# Top_Level.net
KiCad netlist of a schematic drawn in Altium Designer
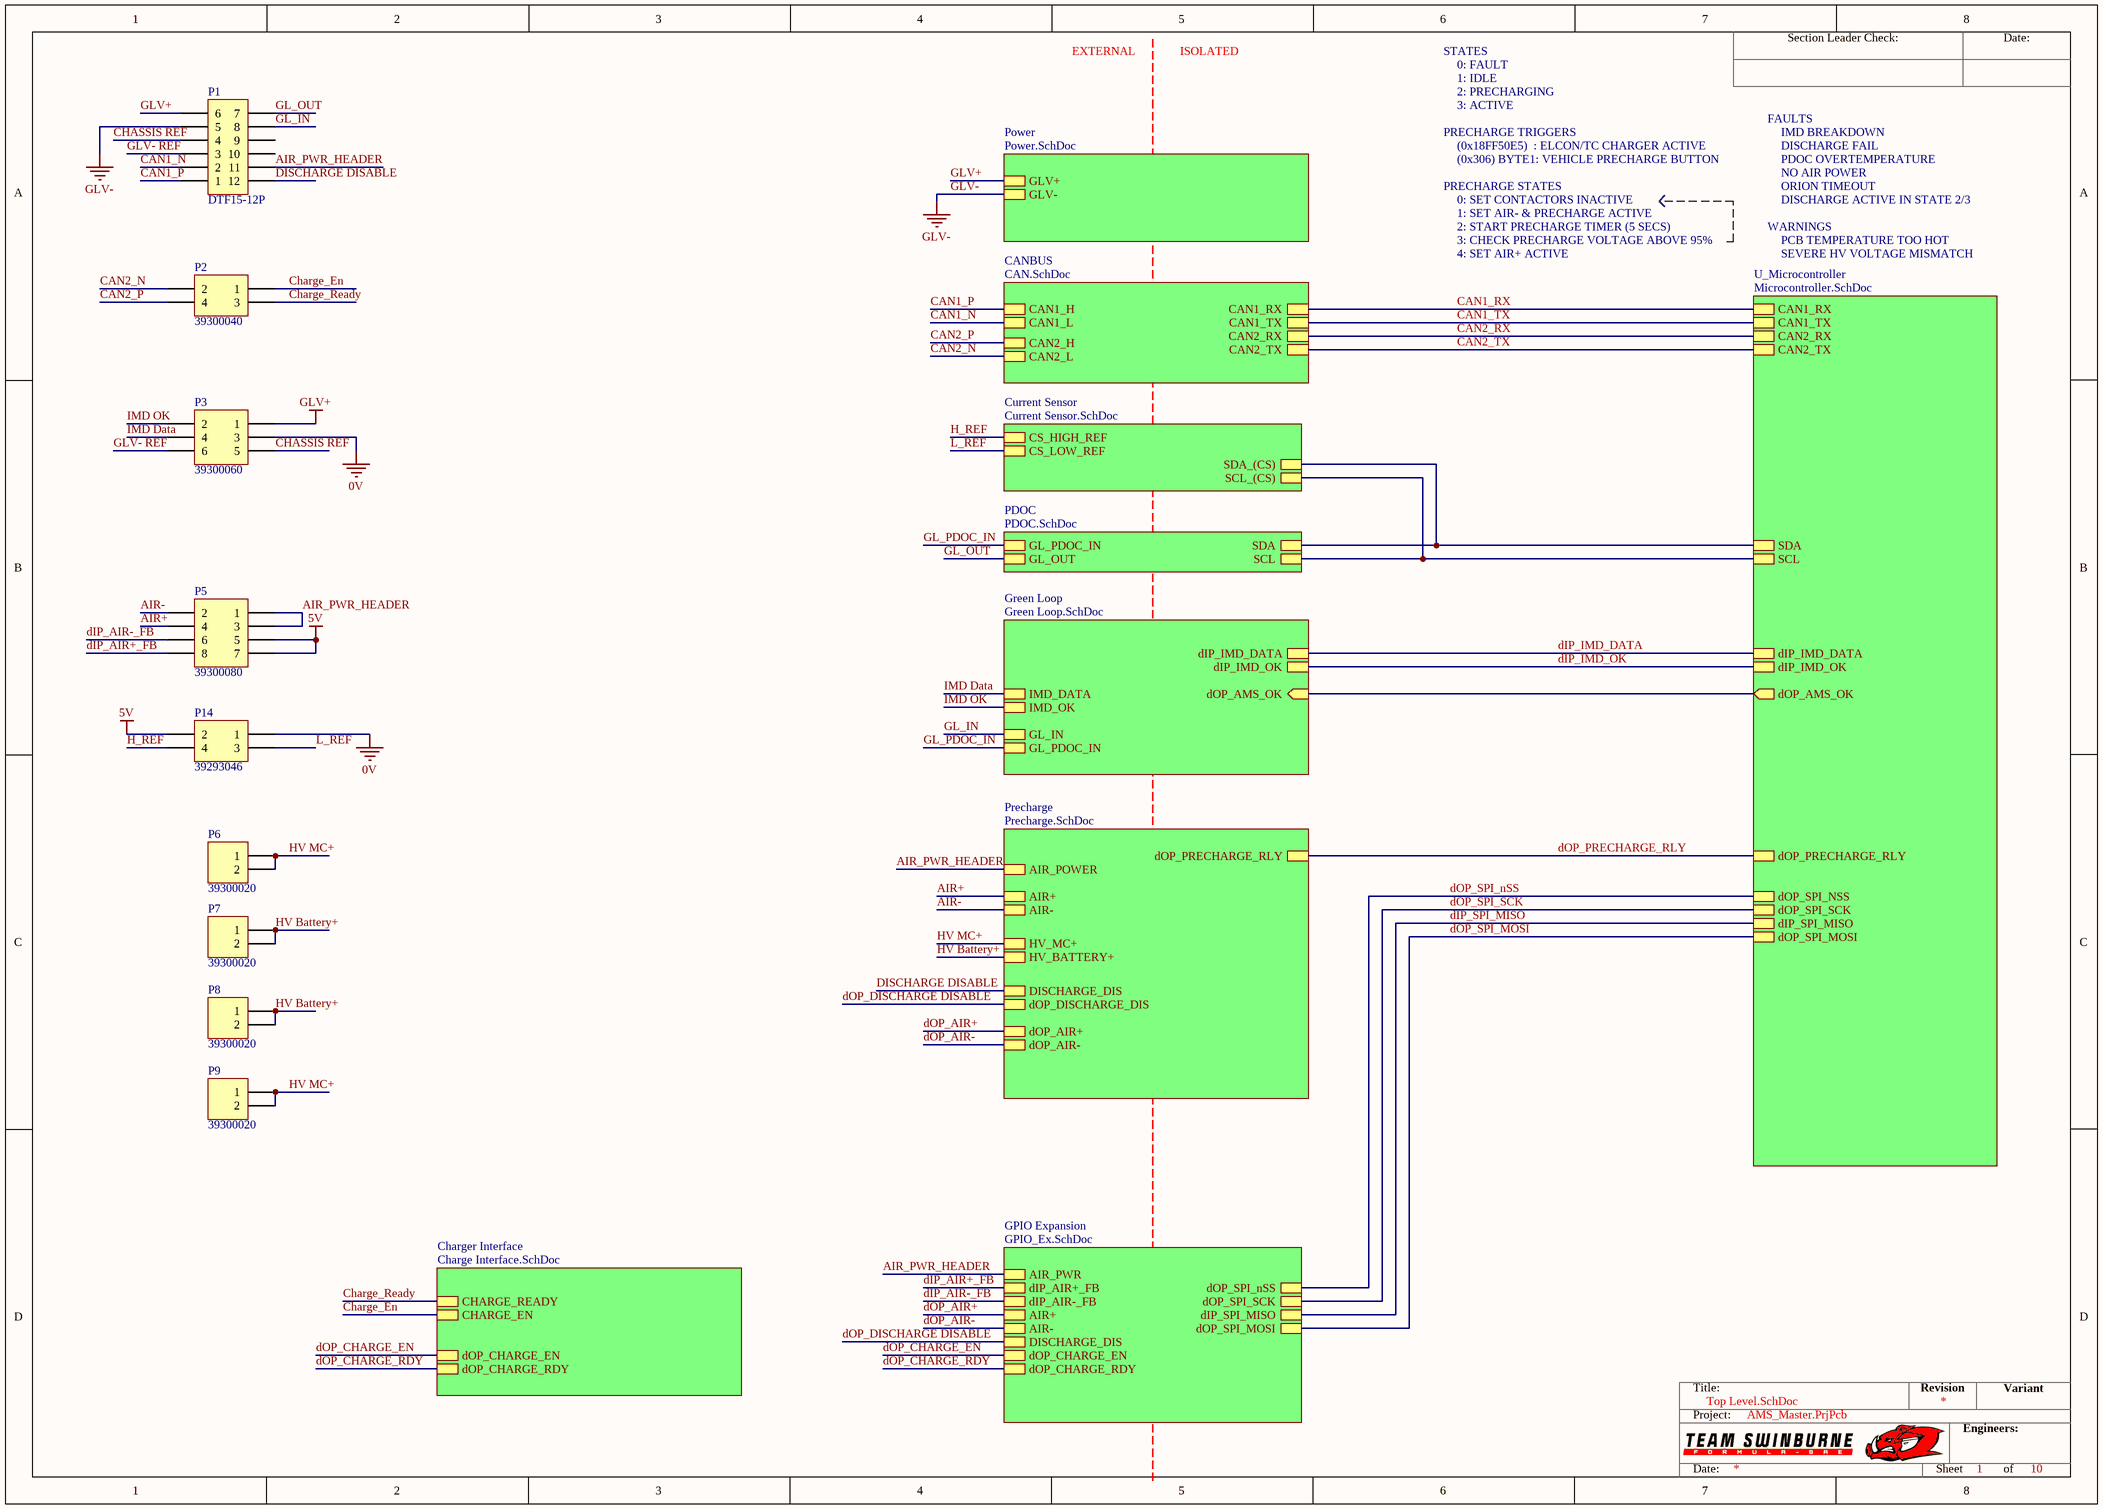
[diagram p0: Top Level.SchDoc]

(export (version "E")
  (design (tool "Eeschema 10.0.6"))
  (components
    (comp (ref "P1")
      (value "DTF15-12P")
      (footprint "DTF15-12P")
      (fields (field (name "DIGIKEY PART NUMBER") "1734-1647-ND") (field (name "CONTACT") "Copper Alloy"))
      (libsource (lib "ts_standard_connectors") (part "DT15-12P"))
    )
    (comp (ref "P2")
      (value "39300040")
      (footprint "39300040")
      (fields (field (name "DIGIKEY PART NUMBER") "WM21352-ND") (field (name "CONTACT") "Tin"))
      (libsource (lib "ts_standard_connectors") (part "4"))
    )
    (comp (ref "P3")
      (value "39300060")
      (footprint "39300060")
      (fields (field (name "DIGIKEY PART NUMBER") "WM21353-ND") (field (name "CONTACT") "Tin"))
      (libsource (lib "ts_standard_connectors") (part "6"))
    )
    (comp (ref "P5")
      (value "39300080")
      (footprint "39300080")
      (fields (field (name "DIGIKEY PART NUMBER") "WM21354-ND") (field (name "CONTACT") "Tin"))
      (libsource (lib "ts_standard_connectors") (part "8"))
    )
    (comp (ref "P6")
      (value "39300020")
      (footprint "39300020")
      (fields (field (name "DIGIKEY PART NUMBER") "WM21351-ND") (field (name "CONTACT") "Tin"))
      (libsource (lib "ts_standard_connectors") (part "2"))
    )
    (comp (ref "P7")
      (value "39300020")
      (footprint "39300020")
      (fields (field (name "DIGIKEY PART NUMBER") "WM21351-ND") (field (name "CONTACT") "Tin"))
      (libsource (lib "ts_standard_connectors") (part "2"))
    )
    (comp (ref "P8")
      (value "39300020")
      (footprint "39300020")
      (fields (field (name "DIGIKEY PART NUMBER") "WM21351-ND") (field (name "CONTACT") "Tin"))
      (libsource (lib "ts_standard_connectors") (part "2"))
    )
    (comp (ref "P9")
      (value "39300020")
      (footprint "39300020")
      (fields (field (name "DIGIKEY PART NUMBER") "WM21351-ND") (field (name "CONTACT") "Tin"))
      (libsource (lib "ts_standard_connectors") (part "2"))
    )
    (comp (ref "P14")
      (value "39293046")
      (footprint "39293046")
      (fields (field (name "DIGIKEY PART NUMBER") "WM3844-ND") (field (name "CONTACT") "Tin"))
      (libsource (lib "ts_standard_connectors") (part "4"))
    )
  )
  (nets
    (net (code "1") (name "/AIR+") (class "Default")
      (node (ref "P5") (pin "4") (pinfunction "4_4") (pintype "passive"))
    )
    (net (code "2") (name "/AIR-") (class "Default")
      (node (ref "P5") (pin "2") (pinfunction "2_2") (pintype "passive"))
    )
    (net (code "3") (name "/AIR_PWR_HEADER") (class "Default")
      (node (ref "P1") (pin "11") (pinfunction "11_11") (pintype "passive"))
      (node (ref "P5") (pin "1") (pinfunction "1_1") (pintype "passive"))
      (node (ref "P5") (pin "3") (pinfunction "3_3") (pintype "passive"))
    )
    (net (code "4") (name "/CAN1_N") (class "Default")
      (node (ref "P1") (pin "2") (pinfunction "2_2") (pintype "power_in"))
    )
    (net (code "5") (name "/CAN1_P") (class "Default")
      (node (ref "P1") (pin "1") (pinfunction "1_1") (pintype "power_in"))
    )
    (net (code "8") (name "/CAN2_N") (class "Default")
      (node (ref "P2") (pin "2") (pinfunction "2_2") (pintype "passive"))
    )
    (net (code "9") (name "/CAN2_P") (class "Default")
      (node (ref "P2") (pin "4") (pinfunction "4_4") (pintype "passive"))
    )
    (net (code "12") (name "/CHASSIS REF") (class "Default")
      (node (ref "P1") (pin "4") (pinfunction "4_4") (pintype "power_in"))
      (node (ref "P3") (pin "5") (pinfunction "5_5") (pintype "passive"))
    )
    (net (code "13") (name "/Charge_En") (class "Default")
      (node (ref "P2") (pin "1") (pinfunction "1_1") (pintype "passive"))
    )
    (net (code "14") (name "/Charge_Ready") (class "Default")
      (node (ref "P2") (pin "3") (pinfunction "3_3") (pintype "passive"))
    )
    (net (code "15") (name "/DISCHARGE DISABLE") (class "Default")
      (node (ref "P1") (pin "12") (pinfunction "12_12") (pintype "passive"))
    )
    (net (code "16") (name "/GLV- REF") (class "Default")
      (node (ref "P1") (pin "3") (pinfunction "3_3") (pintype "power_in"))
      (node (ref "P3") (pin "6") (pinfunction "6_6") (pintype "passive"))
    )
    (net (code "17") (name "/GL_IN") (class "Default")
      (node (ref "P1") (pin "8") (pinfunction "8_8") (pintype "passive"))
    )
    (net (code "18") (name "/GL_OUT") (class "Default")
      (node (ref "P1") (pin "7") (pinfunction "7_7") (pintype "passive"))
    )
    (net (code "20") (name "/HV Battery+") (class "Default")
      (node (ref "P7") (pin "1") (pinfunction "1_1") (pintype "passive"))
      (node (ref "P7") (pin "2") (pinfunction "2_2") (pintype "passive"))
      (node (ref "P8") (pin "1") (pinfunction "1_1") (pintype "passive"))
      (node (ref "P8") (pin "2") (pinfunction "2_2") (pintype "passive"))
    )
    (net (code "21") (name "/HV MC+") (class "Default")
      (node (ref "P6") (pin "1") (pinfunction "1_1") (pintype "passive"))
      (node (ref "P6") (pin "2") (pinfunction "2_2") (pintype "passive"))
      (node (ref "P9") (pin "1") (pinfunction "1_1") (pintype "passive"))
      (node (ref "P9") (pin "2") (pinfunction "2_2") (pintype "passive"))
    )
    (net (code "22") (name "/H_REF") (class "Default")
      (node (ref "P14") (pin "4") (pinfunction "4_4") (pintype "passive"))
    )
    (net (code "23") (name "/IMD Data") (class "Default")
      (node (ref "P3") (pin "4") (pinfunction "4_4") (pintype "passive"))
    )
    (net (code "24") (name "/IMD OK") (class "Default")
      (node (ref "P3") (pin "2") (pinfunction "2_2") (pintype "passive"))
    )
    (net (code "25") (name "/L_REF") (class "Default")
      (node (ref "P14") (pin "3") (pinfunction "3_3") (pintype "passive"))
    )
    (net (code "28") (name "/dIP_AIR+_FB") (class "Default")
      (node (ref "P5") (pin "8") (pinfunction "8_8") (pintype "passive"))
    )
    (net (code "29") (name "/dIP_AIR-_FB") (class "Default")
      (node (ref "P5") (pin "6") (pinfunction "6_6") (pintype "passive"))
    )
    (net (code "43") (name "0V") (class "Default")
      (node (ref "P14") (pin "1") (pinfunction "1_1") (pintype "passive"))
      (node (ref "P3") (pin "3") (pinfunction "3_3") (pintype "passive"))
    )
    (net (code "44") (name "5V") (class "Default")
      (node (ref "P14") (pin "2") (pinfunction "2_2") (pintype "passive"))
      (node (ref "P5") (pin "5") (pinfunction "5_5") (pintype "passive"))
      (node (ref "P5") (pin "7") (pinfunction "7_7") (pintype "passive"))
    )
    (net (code "45") (name "GLV+") (class "Default")
      (node (ref "P1") (pin "6") (pinfunction "6_6") (pintype "power_in"))
      (node (ref "P3") (pin "1") (pinfunction "1_1") (pintype "passive"))
    )
    (net (code "46") (name "GLV-") (class "Default")
      (node (ref "P1") (pin "5") (pinfunction "5_5") (pintype "power_in"))
    )
    (net (code "47") (name "unconnected-(P1-Pad9)") (class "Default")
      (node (ref "P1") (pin "9") (pinfunction "9_9") (pintype "passive"))
    )
    (net (code "48") (name "unconnected-(P1-Pad10)") (class "Default")
      (node (ref "P1") (pin "10") (pinfunction "10_10") (pintype "passive"))
    )
  )
)
